# generator-controller-schematic.net
KiCad netlist of a schematic drawn in EasyEDA
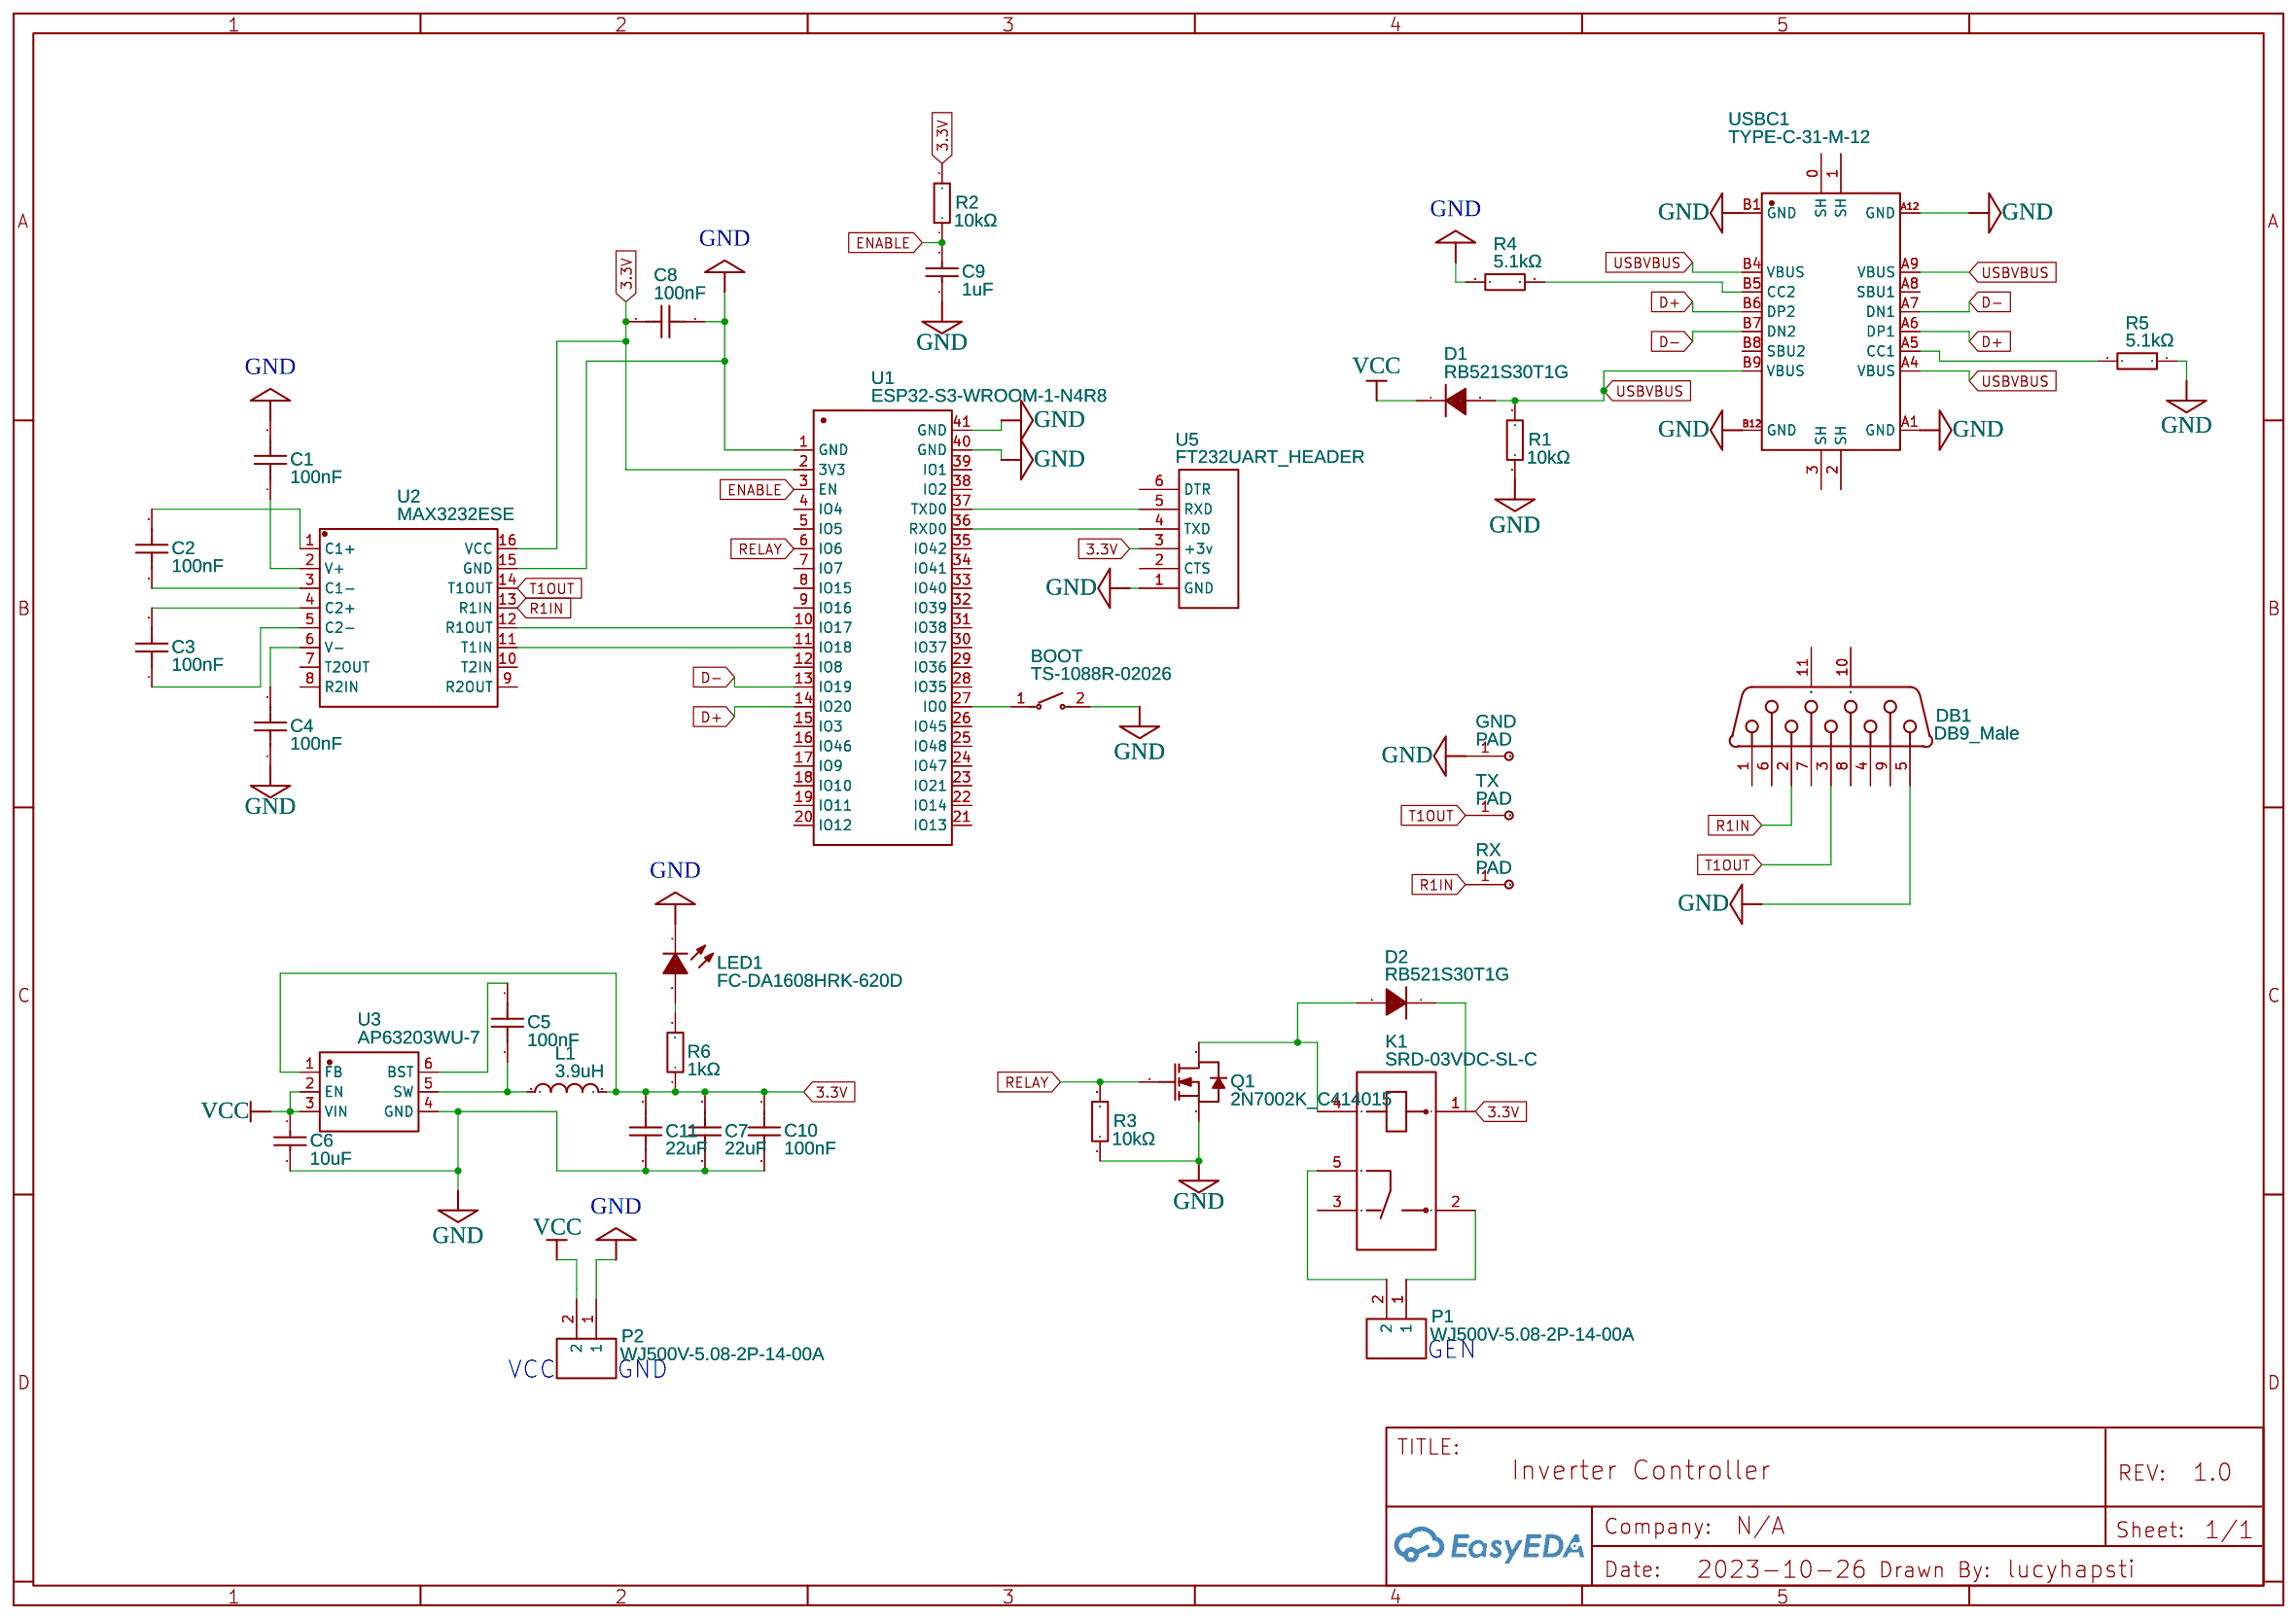
[diagram p0: schematic sheet]

(export (version "E")
  (design (tool "Eeschema 10.0.6"))
  (components
    (comp (ref "BOOT")
      (value "TS-1088R-02026")
      (fields (field (name "Manufacturer") "XUNPU(讯普)"))
      (libsource (lib "") (part "TS-1088R-02026"))
    )
    (comp (ref "C1")
      (value "100nF")
      (fields
        (field (name "Manufacturer Part") "CC0402KRX7R5BB104")
        (field (name "Manufacturer") "YAGEO(国巨)")
      )
      (libsource (lib "") (part "CC0402KRX7R5BB104"))
    )
    (comp (ref "C2")
      (value "100nF")
      (fields
        (field (name "Manufacturer Part") "CC0402KRX7R5BB104")
        (field (name "Manufacturer") "YAGEO(国巨)")
      )
      (libsource (lib "") (part "CC0402KRX7R5BB104"))
    )
    (comp (ref "C3")
      (value "100nF")
      (fields
        (field (name "Manufacturer Part") "CC0402KRX7R5BB104")
        (field (name "Manufacturer") "YAGEO(国巨)")
      )
      (libsource (lib "") (part "CC0402KRX7R5BB104"))
    )
    (comp (ref "C4")
      (value "100nF")
      (fields
        (field (name "Manufacturer Part") "CC0402KRX7R5BB104")
        (field (name "Manufacturer") "YAGEO(国巨)")
      )
      (libsource (lib "") (part "CC0402KRX7R5BB104"))
    )
    (comp (ref "C5")
      (value "100nF")
      (fields
        (field (name "Manufacturer Part") "CC0402KRX7R5BB104")
        (field (name "Manufacturer") "YAGEO(国巨)")
      )
      (libsource (lib "") (part "CC0402KRX7R5BB104_1"))
    )
    (comp (ref "C6")
      (value "10uF")
      (fields
        (field (name "Manufacturer Part") "CL31A106KBHNNNE")
        (field (name "Manufacturer") "SAMSUNG(三星)")
      )
      (libsource (lib "") (part "CL31A106KBHNNNE"))
    )
    (comp (ref "C7")
      (value "22uF")
      (fields
        (field (name "Manufacturer Part") "GRM155R60J226ME11D")
        (field (name "Manufacturer") "muRata(村田)")
      )
      (libsource (lib "") (part "GRM155R60J226ME11D"))
    )
    (comp (ref "C8")
      (value "100nF")
      (fields
        (field (name "Manufacturer Part") "CC0402KRX7R5BB104")
        (field (name "Manufacturer") "YAGEO(国巨)")
      )
      (libsource (lib "") (part "CC0402KRX7R5BB104_2"))
    )
    (comp (ref "C9")
      (value "1uF")
      (fields
        (field (name "Manufacturer Part") "CL05A105KQ5NNNC")
        (field (name "Manufacturer") "SAMSUNG(三星)")
      )
      (libsource (lib "") (part "CL05A105KQ5NNNC"))
    )
    (comp (ref "C10")
      (value "100nF")
      (fields
        (field (name "Manufacturer Part") "CC0402KRX7R5BB104")
        (field (name "Manufacturer") "YAGEO(国巨)")
      )
      (libsource (lib "") (part "CC0402KRX7R5BB104_1"))
    )
    (comp (ref "C11")
      (value "22uF")
      (fields
        (field (name "Manufacturer Part") "GRM155R60J226ME11D")
        (field (name "Manufacturer") "muRata(村田)")
      )
      (libsource (lib "") (part "GRM155R60J226ME11D"))
    )
    (comp (ref "D1")
      (value "RB521S30T1G")
      (fields (field (name "Manufacturer") "onsemi(安森美)"))
      (libsource (lib "") (part "RB521S30T1G_1"))
    )
    (comp (ref "D2")
      (value "RB521S30T1G")
      (fields (field (name "Manufacturer") "onsemi(安森美)"))
      (libsource (lib "") (part "RB521S30T1G"))
    )
    (comp (ref "DB1")
      (value "DB9_Male")
      (fields (field (name "Manufacturer") "Ckmtw"))
      (libsource (lib "") (part "DB9_Male"))
    )
    (comp (ref "GND") (value "PAD") (libsource (lib "") (part "PAD_2")))
    (comp (ref "K1")
      (value "SRD-03VDC-SL-C")
      (fields (field (name "Manufacturer") "松乐"))
      (libsource (lib "") (part "SRD-03VDC-SL-C"))
    )
    (comp (ref "L1")
      (value "3.9uH")
      (fields (field (name "Manufacturer Part") "SWPA4030S3R9MT") (field (name "Manufacturer") "Sunlord(顺络)"))
      (libsource (lib "") (part "SWPA4030S3R9MT"))
    )
    (comp (ref "LED1")
      (value "FC-DA1608HRK-620D")
      (fields (field (name "Manufacturer Part") "NCD0603R1") (field (name "Manufacturer") "国星光电"))
      (libsource (lib "") (part "FC-DA1608HRK-620D"))
    )
    (comp (ref "P1")
      (value "WJ500V-5.08-2P-14-00A")
      (fields
        (field (name "Manufacturer Part") "WJ500V-5.08-2P")
        (field (name "Manufacturer") "KANGNEX(康奈克斯电气)")
      )
      (libsource (lib "") (part "WJ500V-5.08-2P-14-00A"))
    )
    (comp (ref "P2")
      (value "WJ500V-5.08-2P-14-00A")
      (fields
        (field (name "Manufacturer Part") "WJ500V-5.08-2P")
        (field (name "Manufacturer") "KANGNEX(康奈克斯电气)")
      )
      (libsource (lib "") (part "WJ500V-5.08-2P-14-00A"))
    )
    (comp (ref "Q1")
      (value "2N7002K_C414015")
      (fields (field (name "Manufacturer Part") "2N7002K") (field (name "Manufacturer") "MDD"))
      (libsource (lib "") (part "2N7002K_C414015"))
    )
    (comp (ref "R1")
      (value "10kΩ")
      (fields (field (name "Manufacturer Part") "RC0402FR-0710KL") (field (name "Manufacturer") "YAGEO(国巨)"))
      (libsource (lib "") (part "RC0402FR-0710KL"))
    )
    (comp (ref "R2")
      (value "10kΩ")
      (fields (field (name "Manufacturer Part") "RC0402FR-0710KL") (field (name "Manufacturer") "YAGEO(国巨)"))
      (libsource (lib "") (part "RC0402FR-0710KL"))
    )
    (comp (ref "R3")
      (value "10kΩ")
      (fields (field (name "Manufacturer Part") "RC0402FR-0710KL") (field (name "Manufacturer") "YAGEO(国巨)"))
      (libsource (lib "") (part "RC0402FR-0710KL"))
    )
    (comp (ref "R4")
      (value "5.1kΩ")
      (fields
        (field (name "Manufacturer Part") "0402WGF5101TCE")
        (field (name "Manufacturer") "UNI-ROYAL(厚声)")
      )
      (libsource (lib "") (part "0402WGF5101TCE"))
    )
    (comp (ref "R5")
      (value "5.1kΩ")
      (fields
        (field (name "Manufacturer Part") "0402WGF5101TCE")
        (field (name "Manufacturer") "UNI-ROYAL(厚声)")
      )
      (libsource (lib "") (part "0402WGF5101TCE_1"))
    )
    (comp (ref "R6")
      (value "1kΩ")
      (fields
        (field (name "Manufacturer Part") "0402WGF1001TCE")
        (field (name "Manufacturer") "UNI-ROYAL(厚声)")
      )
      (libsource (lib "") (part "0402WGF1001TCE"))
    )
    (comp (ref "RX") (value "PAD") (libsource (lib "") (part "PAD")))
    (comp (ref "TX") (value "PAD") (libsource (lib "") (part "PAD_1")))
    (comp (ref "U1")
      (value "ESP32-S3-WROOM-1-N4R8")
      (fields (field (name "Manufacturer") "ESPRESSIF(乐鑫)"))
      (libsource (lib "") (part "ESP32-S3-WROOM-1-N4R8"))
    )
    (comp (ref "U2")
      (value "MAX3232ESE")
      (fields (field (name "Manufacturer") "UMW(广东友台半导体)"))
      (libsource (lib "") (part "MAX3232ESE"))
    )
    (comp (ref "U3")
      (value "AP63203WU-7")
      (fields (field (name "Manufacturer") "DIODES(美台)"))
      (libsource (lib "") (part "AP63203WU-7"))
    )
    (comp (ref "U5") (value "FT232UART_HEADER") (libsource (lib "") (part "FT232UART_HEADER")))
    (comp (ref "USBC1")
      (value "TYPE-C-31-M-12")
      (fields (field (name "Manufacturer") "韩国韩荣"))
      (libsource (lib "") (part "TYPE-C-31-M-12"))
    )
  )
  (nets
    (net (code "1") (name "3.3V") (class "Default")
      (node (ref "C10") (pin "1") (pinfunction "1_1") (pintype "unspecified"))
      (node (ref "C11") (pin "2") (pinfunction "2_2") (pintype "unspecified"))
      (node (ref "C7") (pin "2") (pinfunction "2_2") (pintype "unspecified"))
      (node (ref "C8") (pin "1") (pinfunction "1_1") (pintype "unspecified"))
      (node (ref "K1") (pin "1") (pinfunction "1_1") (pintype "unspecified"))
      (node (ref "L1") (pin "2") (pinfunction "2_2") (pintype "unspecified"))
      (node (ref "R2") (pin "2") (pinfunction "2_2") (pintype "input"))
      (node (ref "R6") (pin "1") (pinfunction "1_1") (pintype "input"))
      (node (ref "U1") (pin "2") (pinfunction "3V3_2") (pintype "unspecified"))
      (node (ref "U2") (pin "16") (pinfunction "VCC_16") (pintype "unspecified"))
      (node (ref "U3") (pin "1") (pinfunction "FB_1") (pintype "unspecified"))
      (node (ref "U5") (pin "3") (pinfunction "+3v_3") (pintype "unspecified"))
    )
    (net (code "2") (name "D+") (class "Default")
      (node (ref "U1") (pin "14") (pinfunction "IO20_14") (pintype "unspecified"))
      (node (ref "USBC1") (pin "A6") (pinfunction "DP1_A6") (pintype "unspecified"))
      (node (ref "USBC1") (pin "B6") (pinfunction "DP2_B6") (pintype "unspecified"))
    )
    (net (code "3") (name "D-") (class "Default")
      (node (ref "U1") (pin "13") (pinfunction "IO19_13") (pintype "unspecified"))
      (node (ref "USBC1") (pin "A7") (pinfunction "DN1_A7") (pintype "unspecified"))
      (node (ref "USBC1") (pin "B7") (pinfunction "DN2_B7") (pintype "unspecified"))
    )
    (net (code "4") (name "ENABLE") (class "Default")
      (node (ref "C9") (pin "2") (pinfunction "2_2") (pintype "input"))
      (node (ref "R2") (pin "1") (pinfunction "1_1") (pintype "input"))
      (node (ref "U1") (pin "3") (pinfunction "EN_3") (pintype "unspecified"))
    )
    (net (code "5") (name "GND") (class "Default")
      (node (ref "BOOT") (pin "2") (pinfunction "2_2") (pintype "unspecified"))
      (node (ref "C1") (pin "2") (pinfunction "2_2") (pintype "unspecified"))
      (node (ref "C10") (pin "2") (pinfunction "2_2") (pintype "unspecified"))
      (node (ref "C11") (pin "1") (pinfunction "1_1") (pintype "unspecified"))
      (node (ref "C4") (pin "1") (pinfunction "1_1") (pintype "unspecified"))
      (node (ref "C6") (pin "1") (pinfunction "1_1") (pintype "input"))
      (node (ref "C7") (pin "1") (pinfunction "1_1") (pintype "unspecified"))
      (node (ref "C8") (pin "2") (pinfunction "2_2") (pintype "unspecified"))
      (node (ref "C9") (pin "1") (pinfunction "1_1") (pintype "input"))
      (node (ref "DB1") (pin "5") (pinfunction "5_5") (pintype "input"))
      (node (ref "GND") (pin "1") (pinfunction "Pad_1") (pintype "unspecified"))
      (node (ref "LED1") (pin "1") (pinfunction "K_1") (pintype "input"))
      (node (ref "P2") (pin "1") (pinfunction "1_1") (pintype "unspecified"))
      (node (ref "Q1") (pin "2") (pinfunction "S_2") (pintype "unspecified"))
      (node (ref "R1") (pin "1") (pinfunction "1_1") (pintype "input"))
      (node (ref "R3") (pin "1") (pinfunction "1_1") (pintype "input"))
      (node (ref "R4") (pin "1") (pinfunction "1_1") (pintype "input"))
      (node (ref "R5") (pin "1") (pinfunction "1_1") (pintype "input"))
      (node (ref "U1") (pin "1") (pinfunction "GND_1") (pintype "unspecified"))
      (node (ref "U1") (pin "40") (pinfunction "GND_40") (pintype "unspecified"))
      (node (ref "U1") (pin "41") (pinfunction "GND_41") (pintype "unspecified"))
      (node (ref "U2") (pin "15") (pinfunction "GND_15") (pintype "unspecified"))
      (node (ref "U3") (pin "4") (pinfunction "GND_4") (pintype "unspecified"))
      (node (ref "U5") (pin "1") (pinfunction "GND_1") (pintype "unspecified"))
      (node (ref "USBC1") (pin "A1") (pinfunction "GND_A1") (pintype "unspecified"))
      (node (ref "USBC1") (pin "A12") (pinfunction "GND_A12") (pintype "unspecified"))
      (node (ref "USBC1") (pin "B1") (pinfunction "GND_B1") (pintype "unspecified"))
      (node (ref "USBC1") (pin "B12") (pinfunction "GND_B12") (pintype "unspecified"))
    )
    (net (code "6") (name "Net-(D2-A)") (class "Default")
      (node (ref "D2") (pin "2") (pinfunction "A_2") (pintype "unspecified"))
      (node (ref "K1") (pin "4") (pinfunction "4_4") (pintype "unspecified"))
      (node (ref "Q1") (pin "3") (pinfunction "D_3") (pintype "unspecified"))
    )
    (net (code "7") (name "Net-(K1-Pad2)") (class "Default")
      (node (ref "K1") (pin "2") (pinfunction "2_2") (pintype "unspecified"))
      (node (ref "P1") (pin "1") (pinfunction "1_1") (pintype "unspecified"))
    )
    (net (code "8") (name "Net-(K1-Pad5)") (class "Default")
      (node (ref "K1") (pin "5") (pinfunction "5_5") (pintype "unspecified"))
      (node (ref "P1") (pin "2") (pinfunction "2_2") (pintype "unspecified"))
    )
    (net (code "9") (name "Net-(LED1-A)") (class "Default")
      (node (ref "LED1") (pin "2") (pinfunction "A_2") (pintype "input"))
      (node (ref "R6") (pin "2") (pinfunction "2_2") (pintype "input"))
    )
    (net (code "10") (name "Net-(U1-IO0)") (class "Default")
      (node (ref "BOOT") (pin "1") (pinfunction "1_1") (pintype "unspecified"))
      (node (ref "U1") (pin "27") (pinfunction "IO0_27") (pintype "unspecified"))
    )
    (net (code "11") (name "Net-(U1-IO17)") (class "Default")
      (node (ref "U1") (pin "10") (pinfunction "IO17_10") (pintype "unspecified"))
      (node (ref "U2") (pin "12") (pinfunction "R1OUT_12") (pintype "unspecified"))
    )
    (net (code "12") (name "Net-(U1-IO18)") (class "Default")
      (node (ref "U1") (pin "11") (pinfunction "IO18_11") (pintype "unspecified"))
      (node (ref "U2") (pin "11") (pinfunction "T1IN_11") (pintype "unspecified"))
    )
    (net (code "13") (name "Net-(U1-RXD0)") (class "Default")
      (node (ref "U1") (pin "36") (pinfunction "RXD0_36") (pintype "unspecified"))
      (node (ref "U5") (pin "4") (pinfunction "TXD_4") (pintype "unspecified"))
    )
    (net (code "14") (name "Net-(U1-TXD0)") (class "Default")
      (node (ref "U1") (pin "37") (pinfunction "TXD0_37") (pintype "unspecified"))
      (node (ref "U5") (pin "5") (pinfunction "RXD_5") (pintype "unspecified"))
    )
    (net (code "15") (name "Net-(U2-C1+)") (class "Default")
      (node (ref "C2") (pin "2") (pinfunction "2_2") (pintype "unspecified"))
      (node (ref "U2") (pin "1") (pinfunction "C1+_1") (pintype "unspecified"))
    )
    (net (code "16") (name "Net-(U2-C1-)") (class "Default")
      (node (ref "C2") (pin "1") (pinfunction "1_1") (pintype "unspecified"))
      (node (ref "U2") (pin "3") (pinfunction "C1-_3") (pintype "unspecified"))
    )
    (net (code "17") (name "Net-(U2-C2+)") (class "Default")
      (node (ref "C3") (pin "2") (pinfunction "2_2") (pintype "unspecified"))
      (node (ref "U2") (pin "4") (pinfunction "C2+_4") (pintype "unspecified"))
    )
    (net (code "18") (name "Net-(U2-C2-)") (class "Default")
      (node (ref "C3") (pin "1") (pinfunction "1_1") (pintype "unspecified"))
      (node (ref "U2") (pin "5") (pinfunction "C2-_5") (pintype "unspecified"))
    )
    (net (code "19") (name "Net-(U2-V+)") (class "Default")
      (node (ref "C1") (pin "1") (pinfunction "1_1") (pintype "unspecified"))
      (node (ref "U2") (pin "2") (pinfunction "V+_2") (pintype "unspecified"))
    )
    (net (code "20") (name "Net-(U2-V-)") (class "Default")
      (node (ref "C4") (pin "2") (pinfunction "2_2") (pintype "unspecified"))
      (node (ref "U2") (pin "6") (pinfunction "V-_6") (pintype "unspecified"))
    )
    (net (code "21") (name "Net-(U3-BST)") (class "Default")
      (node (ref "C5") (pin "1") (pinfunction "1_1") (pintype "unspecified"))
      (node (ref "U3") (pin "6") (pinfunction "BST_6") (pintype "unspecified"))
    )
    (net (code "22") (name "Net-(U3-SW)") (class "Default")
      (node (ref "C5") (pin "2") (pinfunction "2_2") (pintype "unspecified"))
      (node (ref "L1") (pin "1") (pinfunction "1_1") (pintype "unspecified"))
      (node (ref "U3") (pin "5") (pinfunction "SW_5") (pintype "unspecified"))
    )
    (net (code "23") (name "Net-(USBC1-CC1)") (class "Default")
      (node (ref "R5") (pin "2") (pinfunction "2_2") (pintype "input"))
      (node (ref "USBC1") (pin "A5") (pinfunction "CC1_A5") (pintype "unspecified"))
    )
    (net (code "24") (name "Net-(USBC1-CC2)") (class "Default")
      (node (ref "R4") (pin "2") (pinfunction "2_2") (pintype "input"))
      (node (ref "USBC1") (pin "B5") (pinfunction "CC2_B5") (pintype "unspecified"))
    )
    (net (code "25") (name "R1IN") (class "Default")
      (node (ref "DB1") (pin "2") (pinfunction "2_2") (pintype "input"))
      (node (ref "RX") (pin "1") (pinfunction "Pad_1") (pintype "unspecified"))
      (node (ref "U2") (pin "13") (pinfunction "R1IN_13") (pintype "unspecified"))
    )
    (net (code "26") (name "RELAY") (class "Default")
      (node (ref "Q1") (pin "1") (pinfunction "G_1") (pintype "unspecified"))
      (node (ref "R3") (pin "2") (pinfunction "2_2") (pintype "input"))
      (node (ref "U1") (pin "6") (pinfunction "IO6_6") (pintype "unspecified"))
    )
    (net (code "27") (name "T1OUT") (class "Default")
      (node (ref "DB1") (pin "3") (pinfunction "3_3") (pintype "input"))
      (node (ref "TX") (pin "1") (pinfunction "Pad_1") (pintype "unspecified"))
      (node (ref "U2") (pin "14") (pinfunction "T1OUT_14") (pintype "unspecified"))
    )
    (net (code "28") (name "USBVBUS") (class "Default")
      (node (ref "D1") (pin "2") (pinfunction "A_2") (pintype "unspecified"))
      (node (ref "R1") (pin "2") (pinfunction "2_2") (pintype "input"))
      (node (ref "USBC1") (pin "A4") (pinfunction "VBUS_A4") (pintype "unspecified"))
      (node (ref "USBC1") (pin "A9") (pinfunction "VBUS_A9") (pintype "unspecified"))
      (node (ref "USBC1") (pin "B4") (pinfunction "VBUS_B4") (pintype "unspecified"))
      (node (ref "USBC1") (pin "B9") (pinfunction "VBUS_B9") (pintype "unspecified"))
    )
    (net (code "29") (name "VCC") (class "Default")
      (node (ref "C6") (pin "2") (pinfunction "2_2") (pintype "input"))
      (node (ref "D1") (pin "1") (pinfunction "C_1") (pintype "unspecified"))
      (node (ref "P2") (pin "2") (pinfunction "2_2") (pintype "unspecified"))
      (node (ref "U3") (pin "2") (pinfunction "EN_2") (pintype "unspecified"))
      (node (ref "U3") (pin "3") (pinfunction "VIN_3") (pintype "unspecified"))
    )
    (net (code "30") (name "unconnected-(D2-C-Pad1)") (class "Default")
      (node (ref "D2") (pin "1") (pinfunction "C_1") (pintype "unspecified"))
    )
    (net (code "31") (name "unconnected-(DB1-MH1-Pad10)") (class "Default")
      (node (ref "DB1") (pin "10") (pinfunction "MH1_10") (pintype "input"))
    )
    (net (code "32") (name "unconnected-(DB1-MH2-Pad11)") (class "Default")
      (node (ref "DB1") (pin "11") (pinfunction "MH2_11") (pintype "input"))
    )
    (net (code "33") (name "unconnected-(DB1-Pad1)") (class "Default")
      (node (ref "DB1") (pin "1") (pinfunction "1_1") (pintype "input"))
    )
    (net (code "34") (name "unconnected-(DB1-Pad4)") (class "Default")
      (node (ref "DB1") (pin "4") (pinfunction "4_4") (pintype "input"))
    )
    (net (code "35") (name "unconnected-(DB1-Pad6)") (class "Default")
      (node (ref "DB1") (pin "6") (pinfunction "6_6") (pintype "input"))
    )
    (net (code "36") (name "unconnected-(DB1-Pad7)") (class "Default")
      (node (ref "DB1") (pin "7") (pinfunction "7_7") (pintype "input"))
    )
    (net (code "37") (name "unconnected-(DB1-Pad8)") (class "Default")
      (node (ref "DB1") (pin "8") (pinfunction "8_8") (pintype "input"))
    )
    (net (code "38") (name "unconnected-(DB1-Pad9)") (class "Default")
      (node (ref "DB1") (pin "9") (pinfunction "9_9") (pintype "input"))
    )
    (net (code "39") (name "unconnected-(K1-Pad3)") (class "Default")
      (node (ref "K1") (pin "3") (pinfunction "3_3") (pintype "unspecified"))
    )
    (net (code "40") (name "unconnected-(U1-IO1-Pad39)") (class "Default")
      (node (ref "U1") (pin "39") (pinfunction "IO1_39") (pintype "unspecified"))
    )
    (net (code "41") (name "unconnected-(U1-IO2-Pad38)") (class "Default")
      (node (ref "U1") (pin "38") (pinfunction "IO2_38") (pintype "unspecified"))
    )
    (net (code "42") (name "unconnected-(U1-IO3-Pad15)") (class "Default")
      (node (ref "U1") (pin "15") (pinfunction "IO3_15") (pintype "unspecified"))
    )
    (net (code "43") (name "unconnected-(U1-IO4-Pad4)") (class "Default")
      (node (ref "U1") (pin "4") (pinfunction "IO4_4") (pintype "unspecified"))
    )
    (net (code "44") (name "unconnected-(U1-IO5-Pad5)") (class "Default")
      (node (ref "U1") (pin "5") (pinfunction "IO5_5") (pintype "unspecified"))
    )
    (net (code "45") (name "unconnected-(U1-IO7-Pad7)") (class "Default")
      (node (ref "U1") (pin "7") (pinfunction "IO7_7") (pintype "unspecified"))
    )
    (net (code "46") (name "unconnected-(U1-IO8-Pad12)") (class "Default")
      (node (ref "U1") (pin "12") (pinfunction "IO8_12") (pintype "unspecified"))
    )
    (net (code "47") (name "unconnected-(U1-IO9-Pad17)") (class "Default")
      (node (ref "U1") (pin "17") (pinfunction "IO9_17") (pintype "unspecified"))
    )
    (net (code "48") (name "unconnected-(U1-IO10-Pad18)") (class "Default")
      (node (ref "U1") (pin "18") (pinfunction "IO10_18") (pintype "unspecified"))
    )
    (net (code "49") (name "unconnected-(U1-IO11-Pad19)") (class "Default")
      (node (ref "U1") (pin "19") (pinfunction "IO11_19") (pintype "unspecified"))
    )
    (net (code "50") (name "unconnected-(U1-IO12-Pad20)") (class "Default")
      (node (ref "U1") (pin "20") (pinfunction "IO12_20") (pintype "unspecified"))
    )
    (net (code "51") (name "unconnected-(U1-IO13-Pad21)") (class "Default")
      (node (ref "U1") (pin "21") (pinfunction "IO13_21") (pintype "unspecified"))
    )
    (net (code "52") (name "unconnected-(U1-IO14-Pad22)") (class "Default")
      (node (ref "U1") (pin "22") (pinfunction "IO14_22") (pintype "unspecified"))
    )
    (net (code "53") (name "unconnected-(U1-IO15-Pad8)") (class "Default")
      (node (ref "U1") (pin "8") (pinfunction "IO15_8") (pintype "unspecified"))
    )
    (net (code "54") (name "unconnected-(U1-IO16-Pad9)") (class "Default")
      (node (ref "U1") (pin "9") (pinfunction "IO16_9") (pintype "unspecified"))
    )
    (net (code "55") (name "unconnected-(U1-IO21-Pad23)") (class "Default")
      (node (ref "U1") (pin "23") (pinfunction "IO21_23") (pintype "unspecified"))
    )
    (net (code "56") (name "unconnected-(U1-IO35-Pad28)") (class "Default")
      (node (ref "U1") (pin "28") (pinfunction "IO35_28") (pintype "unspecified"))
    )
    (net (code "57") (name "unconnected-(U1-IO36-Pad29)") (class "Default")
      (node (ref "U1") (pin "29") (pinfunction "IO36_29") (pintype "unspecified"))
    )
    (net (code "58") (name "unconnected-(U1-IO37-Pad30)") (class "Default")
      (node (ref "U1") (pin "30") (pinfunction "IO37_30") (pintype "unspecified"))
    )
    (net (code "59") (name "unconnected-(U1-IO38-Pad31)") (class "Default")
      (node (ref "U1") (pin "31") (pinfunction "IO38_31") (pintype "unspecified"))
    )
    (net (code "60") (name "unconnected-(U1-IO39-Pad32)") (class "Default")
      (node (ref "U1") (pin "32") (pinfunction "IO39_32") (pintype "unspecified"))
    )
    (net (code "61") (name "unconnected-(U1-IO40-Pad33)") (class "Default")
      (node (ref "U1") (pin "33") (pinfunction "IO40_33") (pintype "unspecified"))
    )
    (net (code "62") (name "unconnected-(U1-IO41-Pad34)") (class "Default")
      (node (ref "U1") (pin "34") (pinfunction "IO41_34") (pintype "unspecified"))
    )
    (net (code "63") (name "unconnected-(U1-IO42-Pad35)") (class "Default")
      (node (ref "U1") (pin "35") (pinfunction "IO42_35") (pintype "unspecified"))
    )
    (net (code "64") (name "unconnected-(U1-IO45-Pad26)") (class "Default")
      (node (ref "U1") (pin "26") (pinfunction "IO45_26") (pintype "unspecified"))
    )
    (net (code "65") (name "unconnected-(U1-IO46-Pad16)") (class "Default")
      (node (ref "U1") (pin "16") (pinfunction "IO46_16") (pintype "unspecified"))
    )
    (net (code "66") (name "unconnected-(U1-IO47-Pad24)") (class "Default")
      (node (ref "U1") (pin "24") (pinfunction "IO47_24") (pintype "unspecified"))
    )
    (net (code "67") (name "unconnected-(U1-IO48-Pad25)") (class "Default")
      (node (ref "U1") (pin "25") (pinfunction "IO48_25") (pintype "unspecified"))
    )
    (net (code "68") (name "unconnected-(U2-R2IN-Pad8)") (class "Default")
      (node (ref "U2") (pin "8") (pinfunction "R2IN_8") (pintype "unspecified"))
    )
    (net (code "69") (name "unconnected-(U2-R2OUT-Pad9)") (class "Default")
      (node (ref "U2") (pin "9") (pinfunction "R2OUT_9") (pintype "unspecified"))
    )
    (net (code "70") (name "unconnected-(U2-T2IN-Pad10)") (class "Default")
      (node (ref "U2") (pin "10") (pinfunction "T2IN_10") (pintype "unspecified"))
    )
    (net (code "71") (name "unconnected-(U2-T2OUT-Pad7)") (class "Default")
      (node (ref "U2") (pin "7") (pinfunction "T2OUT_7") (pintype "unspecified"))
    )
    (net (code "72") (name "unconnected-(U5-CTS-Pad2)") (class "Default")
      (node (ref "U5") (pin "2") (pinfunction "CTS_2") (pintype "unspecified"))
    )
    (net (code "73") (name "unconnected-(U5-DTR-Pad6)") (class "Default")
      (node (ref "U5") (pin "6") (pinfunction "DTR_6") (pintype "unspecified"))
    )
    (net (code "74") (name "unconnected-(USBC1-SBU1-PadA8)") (class "Default")
      (node (ref "USBC1") (pin "A8") (pinfunction "SBU1_A8") (pintype "unspecified"))
    )
    (net (code "75") (name "unconnected-(USBC1-SBU2-PadB8)") (class "Default")
      (node (ref "USBC1") (pin "B8") (pinfunction "SBU2_B8") (pintype "unspecified"))
    )
    (net (code "76") (name "unconnected-(USBC1-SH-Pad0)") (class "Default")
      (node (ref "USBC1") (pin "0") (pinfunction "SH_0") (pintype "unspecified"))
    )
    (net (code "77") (name "unconnected-(USBC1-SH-Pad1)") (class "Default")
      (node (ref "USBC1") (pin "1") (pinfunction "SH_1") (pintype "unspecified"))
    )
    (net (code "78") (name "unconnected-(USBC1-SH-Pad2)") (class "Default")
      (node (ref "USBC1") (pin "2") (pinfunction "SH_2") (pintype "unspecified"))
    )
    (net (code "79") (name "unconnected-(USBC1-SH-Pad3)") (class "Default")
      (node (ref "USBC1") (pin "3") (pinfunction "SH_3") (pintype "unspecified"))
    )
  )
)
